# Arduino_to_G2LaunchPad.net
KiCad netlist of a schematic drawn in Altium Designer
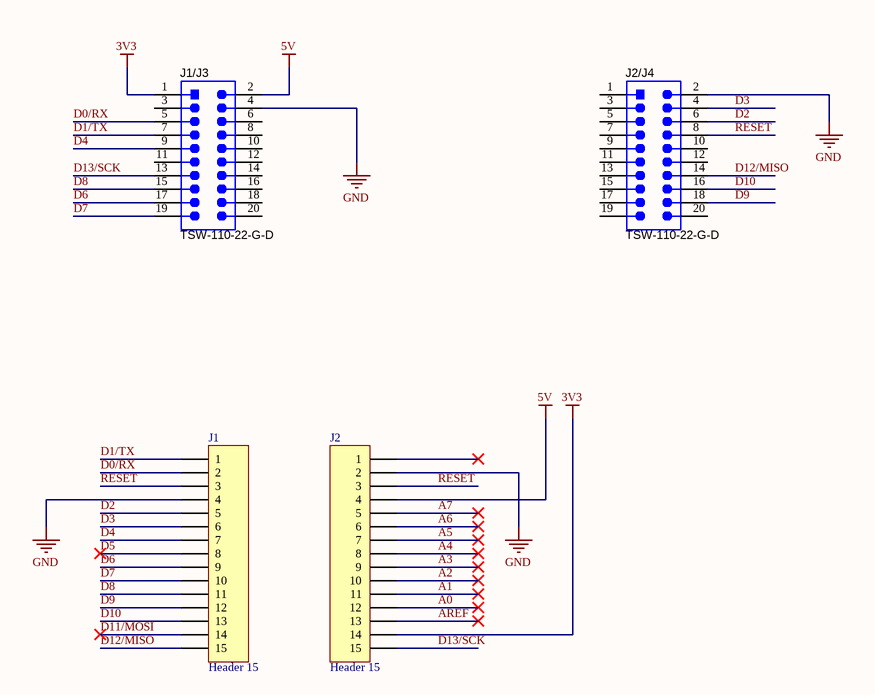
[diagram p0: Arduino_to_G2LaunchPad.SchDoc]

(export (version "E")
  (design (tool "Eeschema 10.0.6"))
  (components
    (comp (ref "J1")
      (value "Header 15")
      (footprint "HDR1X15")
      (description "Header, 15-Pin")
      (fields (field (name "PUBLISHER") "Altium Limited"))
      (libsource (lib "Miscellaneous Connectors") (part "Header 15"))
    )
    (comp (ref "J1/J3")
      (value "TSW-110-22-G-D")
      (footprint "Samtec_TSW-110-22-x-D")
      (description "Header, 2.54mm, 10x2, Gold, TH")
      (fields
        (field (name "MANUFACTURER") "Samtec")
        (field (name "SYMBOLCREATOR") "a0412235")
        (field (name "PUBLISHER") "Texas Instruments")
      )
      (libsource (lib "Connectors_Samtec1") (part "TSW-110-22-G-D"))
    )
    (comp (ref "J2")
      (value "Header 15")
      (footprint "HDR1X15")
      (description "Header, 15-Pin")
      (fields (field (name "PUBLISHER") "Altium Limited"))
      (libsource (lib "") (part "Header 15_1"))
    )
    (comp (ref "J2/J4")
      (value "TSW-110-22-G-D")
      (footprint "Samtec_TSW-110-22-x-D")
      (description "Header, 2.54mm, 10x2, Gold, TH")
      (fields
        (field (name "MANUFACTURER") "Samtec")
        (field (name "SYMBOLCREATOR") "a0412235")
        (field (name "PUBLISHER") "Texas Instruments")
      )
      (libsource (lib "Connectors_Samtec1") (part "TSW-110-22-G-D"))
    )
  )
  (nets
    (net (code "1") (name "/A0") (class "Default")
      (node (ref "J2") (pin "12") (pinfunction "12_12") (pintype "passive+no_connect"))
    )
    (net (code "2") (name "/A1") (class "Default")
      (node (ref "J2") (pin "11") (pinfunction "11_11") (pintype "passive+no_connect"))
    )
    (net (code "3") (name "/A2") (class "Default")
      (node (ref "J2") (pin "10") (pinfunction "10_10") (pintype "passive+no_connect"))
    )
    (net (code "4") (name "/A3") (class "Default")
      (node (ref "J2") (pin "9") (pinfunction "9_9") (pintype "passive+no_connect"))
    )
    (net (code "5") (name "/A4") (class "Default")
      (node (ref "J2") (pin "8") (pinfunction "8_8") (pintype "passive+no_connect"))
    )
    (net (code "6") (name "/A5") (class "Default")
      (node (ref "J2") (pin "7") (pinfunction "7_7") (pintype "passive+no_connect"))
    )
    (net (code "7") (name "/A6") (class "Default")
      (node (ref "J2") (pin "6") (pinfunction "6_6") (pintype "passive+no_connect"))
    )
    (net (code "8") (name "/A7") (class "Default")
      (node (ref "J2") (pin "5") (pinfunction "5_5") (pintype "passive+no_connect"))
    )
    (net (code "9") (name "/AREF") (class "Default")
      (node (ref "J2") (pin "13") (pinfunction "13_13") (pintype "passive+no_connect"))
    )
    (net (code "10") (name "/D0{slash}RX") (class "Default")
      (node (ref "J1") (pin "2") (pinfunction "2_2") (pintype "passive"))
      (node (ref "J1/J3") (pin "5") (pinfunction "5_5") (pintype "passive"))
    )
    (net (code "11") (name "/D1{slash}TX") (class "Default")
      (node (ref "J1") (pin "1") (pinfunction "1_1") (pintype "passive"))
      (node (ref "J1/J3") (pin "7") (pinfunction "7_7") (pintype "passive"))
    )
    (net (code "12") (name "/D2") (class "Default")
      (node (ref "J1") (pin "5") (pinfunction "5_5") (pintype "passive"))
      (node (ref "J2/J4") (pin "6") (pinfunction "6_6") (pintype "passive"))
    )
    (net (code "13") (name "/D3") (class "Default")
      (node (ref "J1") (pin "6") (pinfunction "6_6") (pintype "passive"))
      (node (ref "J2/J4") (pin "4") (pinfunction "4_4") (pintype "passive"))
    )
    (net (code "14") (name "/D4") (class "Default")
      (node (ref "J1") (pin "7") (pinfunction "7_7") (pintype "passive"))
      (node (ref "J1/J3") (pin "9") (pinfunction "9_9") (pintype "passive"))
    )
    (net (code "15") (name "/D5") (class "Default")
      (node (ref "J1") (pin "8") (pinfunction "8_8") (pintype "passive+no_connect"))
    )
    (net (code "16") (name "/D6") (class "Default")
      (node (ref "J1") (pin "9") (pinfunction "9_9") (pintype "passive"))
      (node (ref "J1/J3") (pin "17") (pinfunction "17_17") (pintype "passive"))
    )
    (net (code "17") (name "/D7") (class "Default")
      (node (ref "J1") (pin "10") (pinfunction "10_10") (pintype "passive"))
      (node (ref "J1/J3") (pin "19") (pinfunction "19_19") (pintype "passive"))
    )
    (net (code "18") (name "/D8") (class "Default")
      (node (ref "J1") (pin "11") (pinfunction "11_11") (pintype "passive"))
      (node (ref "J1/J3") (pin "15") (pinfunction "15_15") (pintype "passive"))
    )
    (net (code "19") (name "/D9") (class "Default")
      (node (ref "J1") (pin "12") (pinfunction "12_12") (pintype "passive"))
      (node (ref "J2/J4") (pin "18") (pinfunction "18_18") (pintype "passive"))
    )
    (net (code "20") (name "/D10") (class "Default")
      (node (ref "J1") (pin "13") (pinfunction "13_13") (pintype "passive"))
      (node (ref "J2/J4") (pin "16") (pinfunction "16_16") (pintype "passive"))
    )
    (net (code "21") (name "/D11{slash}MOSI") (class "Default")
      (node (ref "J1") (pin "14") (pinfunction "14_14") (pintype "passive+no_connect"))
    )
    (net (code "22") (name "/D12{slash}MISO") (class "Default")
      (node (ref "J1") (pin "15") (pinfunction "15_15") (pintype "passive"))
      (node (ref "J2/J4") (pin "14") (pinfunction "14_14") (pintype "passive"))
    )
    (net (code "23") (name "/D13{slash}SCK") (class "Default")
      (node (ref "J1/J3") (pin "13") (pinfunction "13_13") (pintype "passive"))
      (node (ref "J2") (pin "15") (pinfunction "15_15") (pintype "passive"))
    )
    (net (code "24") (name "/RESET") (class "Default")
      (node (ref "J1") (pin "3") (pinfunction "3_3") (pintype "passive"))
      (node (ref "J2") (pin "3") (pinfunction "3_3") (pintype "passive"))
      (node (ref "J2/J4") (pin "8") (pinfunction "8_8") (pintype "passive"))
    )
    (net (code "25") (name "3V3") (class "Default")
      (node (ref "J1/J3") (pin "1") (pinfunction "1_1") (pintype "passive"))
      (node (ref "J2") (pin "14") (pinfunction "14_14") (pintype "passive"))
    )
    (net (code "26") (name "5V") (class "Default")
      (node (ref "J1/J3") (pin "2") (pinfunction "2_2") (pintype "passive"))
      (node (ref "J2") (pin "4") (pinfunction "4_4") (pintype "passive"))
    )
    (net (code "27") (name "GND") (class "Default")
      (node (ref "J1") (pin "4") (pinfunction "4_4") (pintype "passive"))
      (node (ref "J1/J3") (pin "4") (pinfunction "4_4") (pintype "passive"))
      (node (ref "J2") (pin "2") (pinfunction "2_2") (pintype "passive"))
      (node (ref "J2/J4") (pin "2") (pinfunction "2_2") (pintype "passive"))
    )
    (net (code "28") (name "unconnected-(J1/J3-Pad3)") (class "Default")
      (node (ref "J1/J3") (pin "3") (pinfunction "3_3") (pintype "passive"))
    )
    (net (code "29") (name "unconnected-(J1/J3-Pad6)") (class "Default")
      (node (ref "J1/J3") (pin "6") (pinfunction "6_6") (pintype "passive"))
    )
    (net (code "30") (name "unconnected-(J1/J3-Pad8)") (class "Default")
      (node (ref "J1/J3") (pin "8") (pinfunction "8_8") (pintype "passive"))
    )
    (net (code "31") (name "unconnected-(J1/J3-Pad10)") (class "Default")
      (node (ref "J1/J3") (pin "10") (pinfunction "10_10") (pintype "passive"))
    )
    (net (code "32") (name "unconnected-(J1/J3-Pad11)") (class "Default")
      (node (ref "J1/J3") (pin "11") (pinfunction "11_11") (pintype "passive"))
    )
    (net (code "33") (name "unconnected-(J1/J3-Pad12)") (class "Default")
      (node (ref "J1/J3") (pin "12") (pinfunction "12_12") (pintype "passive"))
    )
    (net (code "34") (name "unconnected-(J1/J3-Pad14)") (class "Default")
      (node (ref "J1/J3") (pin "14") (pinfunction "14_14") (pintype "passive"))
    )
    (net (code "35") (name "unconnected-(J1/J3-Pad16)") (class "Default")
      (node (ref "J1/J3") (pin "16") (pinfunction "16_16") (pintype "passive"))
    )
    (net (code "36") (name "unconnected-(J1/J3-Pad18)") (class "Default")
      (node (ref "J1/J3") (pin "18") (pinfunction "18_18") (pintype "passive"))
    )
    (net (code "37") (name "unconnected-(J1/J3-Pad20)") (class "Default")
      (node (ref "J1/J3") (pin "20") (pinfunction "20_20") (pintype "passive"))
    )
    (net (code "38") (name "unconnected-(J2-Pad1)") (class "Default")
      (node (ref "J2") (pin "1") (pinfunction "1_1") (pintype "passive+no_connect"))
    )
    (net (code "39") (name "unconnected-(J2/J4-Pad1)") (class "Default")
      (node (ref "J2/J4") (pin "1") (pinfunction "1_1") (pintype "passive"))
    )
    (net (code "40") (name "unconnected-(J2/J4-Pad3)") (class "Default")
      (node (ref "J2/J4") (pin "3") (pinfunction "3_3") (pintype "passive"))
    )
    (net (code "41") (name "unconnected-(J2/J4-Pad5)") (class "Default")
      (node (ref "J2/J4") (pin "5") (pinfunction "5_5") (pintype "passive"))
    )
    (net (code "42") (name "unconnected-(J2/J4-Pad7)") (class "Default")
      (node (ref "J2/J4") (pin "7") (pinfunction "7_7") (pintype "passive"))
    )
    (net (code "43") (name "unconnected-(J2/J4-Pad9)") (class "Default")
      (node (ref "J2/J4") (pin "9") (pinfunction "9_9") (pintype "passive"))
    )
    (net (code "44") (name "unconnected-(J2/J4-Pad10)") (class "Default")
      (node (ref "J2/J4") (pin "10") (pinfunction "10_10") (pintype "passive"))
    )
    (net (code "45") (name "unconnected-(J2/J4-Pad11)") (class "Default")
      (node (ref "J2/J4") (pin "11") (pinfunction "11_11") (pintype "passive"))
    )
    (net (code "46") (name "unconnected-(J2/J4-Pad12)") (class "Default")
      (node (ref "J2/J4") (pin "12") (pinfunction "12_12") (pintype "passive"))
    )
    (net (code "47") (name "unconnected-(J2/J4-Pad13)") (class "Default")
      (node (ref "J2/J4") (pin "13") (pinfunction "13_13") (pintype "passive"))
    )
    (net (code "48") (name "unconnected-(J2/J4-Pad15)") (class "Default")
      (node (ref "J2/J4") (pin "15") (pinfunction "15_15") (pintype "passive"))
    )
    (net (code "49") (name "unconnected-(J2/J4-Pad17)") (class "Default")
      (node (ref "J2/J4") (pin "17") (pinfunction "17_17") (pintype "passive"))
    )
    (net (code "50") (name "unconnected-(J2/J4-Pad19)") (class "Default")
      (node (ref "J2/J4") (pin "19") (pinfunction "19_19") (pintype "passive"))
    )
    (net (code "51") (name "unconnected-(J2/J4-Pad20)") (class "Default")
      (node (ref "J2/J4") (pin "20") (pinfunction "20_20") (pintype "passive"))
    )
  )
)
